# mass_slit.net
KiCad netlist of a schematic drawn in EAGLE
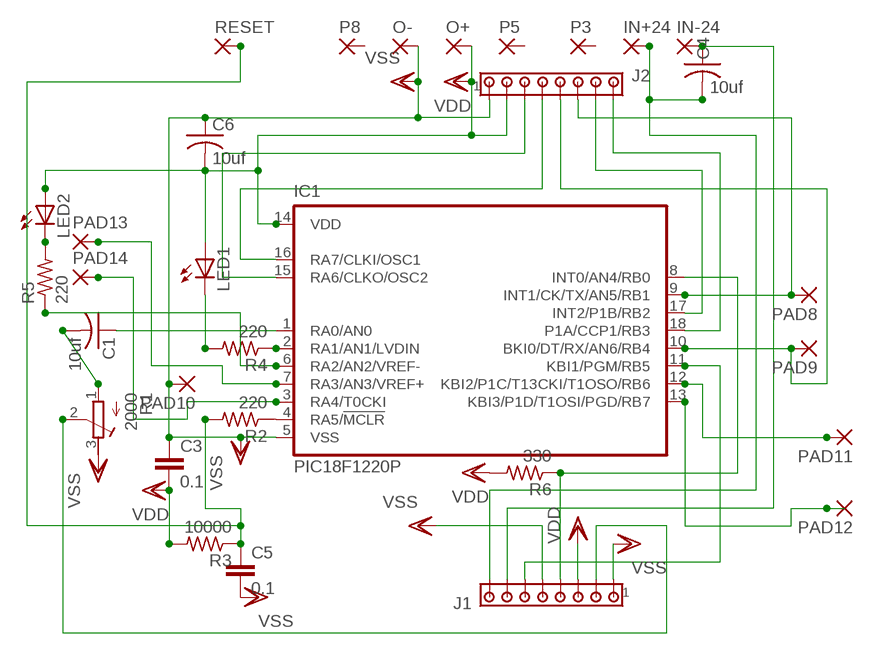
[diagram p0: schematic, sheet 1]

(export (version "E")
  (design (tool "Eeschema 10.0.6"))
  (components
    (comp (ref "C1")
      (value "10uf")
      (footprint "eagle-import:C025-040X050")
      (libsource (lib "eagle-import") (part "C-US025-040X050"))
    )
    (comp (ref "C3")
      (value "0.1")
      (footprint "eagle-import:C5B2.5")
      (libsource (lib "eagle-import") (part "C5/2.5"))
    )
    (comp (ref "C4")
      (value "10uf")
      (footprint "eagle-import:C025-040X050")
      (libsource (lib "eagle-import") (part "C-US025-040X050"))
    )
    (comp (ref "C5")
      (value "0.1")
      (footprint "eagle-import:C5B2.5")
      (libsource (lib "eagle-import") (part "C5/2.5"))
    )
    (comp (ref "C6")
      (value "10uf")
      (footprint "eagle-import:C025-040X050")
      (libsource (lib "eagle-import") (part "C-US025-040X050"))
    )
    (comp (ref "IC1")
      (value "PIC18F1220P")
      (footprint "eagle-import:DIL18")
      (fields (field (name "MF") "MICROCHIP") (field (name "MPN") "PIC18F1220-I/P"))
      (libsource (lib "eagle-import") (part "PIC18F120P2"))
    )
    (comp (ref "IN+24")
      (value "1,6/0,9")
      (footprint "eagle-import:1,6_0,9")
      (libsource (lib "eagle-import") (part "1,6/0,9"))
    )
    (comp (ref "IN-24")
      (value "1,6/0,9")
      (footprint "eagle-import:1,6_0,9")
      (libsource (lib "eagle-import") (part "1,6/0,9"))
    )
    (comp (ref "J1")
      (value "MTA08-100")
      (footprint "eagle-import:10X08MTA")
      (libsource (lib "eagle-import") (part "MTA08-100"))
    )
    (comp (ref "J2")
      (value "MTA08-100")
      (footprint "eagle-import:10X08MTA")
      (libsource (lib "eagle-import") (part "MTA08-100"))
    )
    (comp (ref "LED1")
      (value "LED3MM")
      (footprint "eagle-import:LED3MM")
      (libsource (lib "eagle-import") (part "LED3MM"))
    )
    (comp (ref "LED2")
      (value "LED3MM")
      (footprint "eagle-import:LED3MM")
      (libsource (lib "eagle-import") (part "LED3MM"))
    )
    (comp (ref "O+")
      (value "1,6/0,9")
      (footprint "eagle-import:1,6_0,9")
      (libsource (lib "eagle-import") (part "1,6/0,9"))
    )
    (comp (ref "O-")
      (value "1,6/0,9")
      (footprint "eagle-import:1,6_0,9")
      (libsource (lib "eagle-import") (part "1,6/0,9"))
    )
    (comp (ref "P3")
      (value "1,6/0,9")
      (footprint "eagle-import:1,6_0,9")
      (libsource (lib "eagle-import") (part "1,6/0,9"))
    )
    (comp (ref "P5")
      (value "1,6/0,9")
      (footprint "eagle-import:1,6_0,9")
      (libsource (lib "eagle-import") (part "1,6/0,9"))
    )
    (comp (ref "P8")
      (value "1,6/0,9")
      (footprint "eagle-import:1,6_0,9")
      (libsource (lib "eagle-import") (part "1,6/0,9"))
    )
    (comp (ref "PAD8")
      (value "1,6/0,9")
      (footprint "eagle-import:1,6_0,9")
      (libsource (lib "eagle-import") (part "1,6/0,9"))
    )
    (comp (ref "PAD9")
      (value "1,6/0,9")
      (footprint "eagle-import:1,6_0,9")
      (libsource (lib "eagle-import") (part "1,6/0,9"))
    )
    (comp (ref "PAD10")
      (value "1,6/0,9")
      (footprint "eagle-import:1,6_0,9")
      (libsource (lib "eagle-import") (part "1,6/0,9"))
    )
    (comp (ref "PAD11")
      (value "1,6/0,9")
      (footprint "eagle-import:1,6_0,9")
      (libsource (lib "eagle-import") (part "1,6/0,9"))
    )
    (comp (ref "PAD12")
      (value "1,6/0,9")
      (footprint "eagle-import:1,6_0,9")
      (libsource (lib "eagle-import") (part "1,6/0,9"))
    )
    (comp (ref "PAD13")
      (value "1,6/0,9")
      (footprint "eagle-import:1,6_0,9")
      (libsource (lib "eagle-import") (part "1,6/0,9"))
    )
    (comp (ref "PAD14")
      (value "1,6/0,9")
      (footprint "eagle-import:1,6_0,9")
      (libsource (lib "eagle-import") (part "1,6/0,9"))
    )
    (comp (ref "R1")
      (value "2000")
      (footprint "eagle-import:RTRIM3339P")
      (libsource (lib "eagle-import") (part "R-TRIMM3339P"))
    )
    (comp (ref "R2")
      (value "220")
      (footprint "eagle-import:0204V")
      (libsource (lib "eagle-import") (part "R-US_0204/2V"))
    )
    (comp (ref "R3")
      (value "10000")
      (footprint "eagle-import:0204V")
      (libsource (lib "eagle-import") (part "R-US_0204/2V"))
    )
    (comp (ref "R4")
      (value "220")
      (footprint "eagle-import:0204V")
      (libsource (lib "eagle-import") (part "R-US_0204/2V"))
    )
    (comp (ref "R5")
      (value "220")
      (footprint "eagle-import:0204V")
      (libsource (lib "eagle-import") (part "R-US_0204/2V"))
    )
    (comp (ref "R6")
      (value "330")
      (footprint "eagle-import:0204V")
      (libsource (lib "eagle-import") (part "R-US_0204/2V"))
    )
    (comp (ref "RESET")
      (value "1,6/0,9")
      (footprint "eagle-import:1,6_0,9")
      (libsource (lib "eagle-import") (part "1,6/0,9"))
    )
  )
  (nets
    (net (code "1") (name "Net-(IC1-BKI0{slash}DT{slash}RX{slash}AN6{slash}RB4)") (class "Default")
      (node (ref "IC1") (pin "10") (pinfunction "BKI0/DT/RX/AN6/RB4_10") (pintype "bidirectional"))
      (node (ref "J2") (pin "5") (pinfunction "5_5") (pintype "passive"))
      (node (ref "PAD9") (pin "1") (pinfunction "P_1") (pintype "passive"))
    )
    (net (code "2") (name "Net-(IC1-INT0{slash}AN4{slash}RB0)") (class "Default")
      (node (ref "IC1") (pin "8") (pinfunction "INT0/AN4/RB0_8") (pintype "bidirectional"))
      (node (ref "J1") (pin "4") (pinfunction "4_4") (pintype "passive"))
      (node (ref "R6") (pin "1") (pinfunction "1_1") (pintype "passive"))
    )
    (net (code "3") (name "Net-(IC1-INT1{slash}CK{slash}TX{slash}AN5{slash}RB1)") (class "Default")
      (node (ref "IC1") (pin "9") (pinfunction "INT1/CK/TX/AN5/RB1_9") (pintype "bidirectional"))
      (node (ref "J2") (pin "6") (pinfunction "6_6") (pintype "passive"))
      (node (ref "PAD8") (pin "1") (pinfunction "P_1") (pintype "passive"))
    )
    (net (code "4") (name "Net-(IC1-INT2{slash}P1B{slash}RB2)") (class "Default")
      (node (ref "IC1") (pin "17") (pinfunction "INT2/P1B/RB2_17") (pintype "bidirectional"))
      (node (ref "J2") (pin "7") (pinfunction "7_7") (pintype "passive"))
    )
    (net (code "5") (name "Net-(IC1-KBI1{slash}PGM{slash}RB5)") (class "Default")
      (node (ref "IC1") (pin "11") (pinfunction "KBI1/PGM/RB5_11") (pintype "bidirectional"))
      (node (ref "J1") (pin "6") (pinfunction "6_6") (pintype "passive"))
    )
    (net (code "6") (name "Net-(IC1-KBI2{slash}P1C{slash}T13CKI{slash}T1OSO{slash}RB6)") (class "Default")
      (node (ref "IC1") (pin "12") (pinfunction "KBI2/P1C/T13CKI/T1OSO/RB6_12") (pintype "bidirectional"))
      (node (ref "PAD11") (pin "1") (pinfunction "P_1") (pintype "passive"))
    )
    (net (code "7") (name "Net-(IC1-KBI3{slash}P1D{slash}T1OSI{slash}PGD{slash}RB7)") (class "Default")
      (node (ref "IC1") (pin "13") (pinfunction "KBI3/P1D/T1OSI/PGD/RB7_13") (pintype "bidirectional"))
      (node (ref "PAD12") (pin "1") (pinfunction "P_1") (pintype "passive"))
    )
    (net (code "8") (name "Net-(IC1-P1A{slash}CCP1{slash}RB3)") (class "Default")
      (node (ref "IC1") (pin "18") (pinfunction "P1A/CCP1/RB3_18") (pintype "bidirectional"))
      (node (ref "J2") (pin "8") (pinfunction "8_8") (pintype "passive"))
    )
    (net (code "9") (name "Net-(IC1-RA0{slash}AN0)") (class "Default")
      (node (ref "C1") (pin "1") (pinfunction "1_1") (pintype "passive"))
      (node (ref "IC1") (pin "1") (pinfunction "RA0/AN0_1") (pintype "bidirectional"))
    )
    (net (code "10") (name "Net-(IC1-RA1{slash}AN1{slash}LVDIN)") (class "Default")
      (node (ref "IC1") (pin "2") (pinfunction "RA1/AN1/LVDIN_2") (pintype "bidirectional"))
      (node (ref "R4") (pin "1") (pinfunction "1_1") (pintype "passive"))
    )
    (net (code "11") (name "Net-(IC1-RA2{slash}AN2{slash}VREF-)") (class "Default")
      (node (ref "IC1") (pin "6") (pinfunction "RA2/AN2/VREF-_6") (pintype "bidirectional"))
      (node (ref "R5") (pin "1") (pinfunction "1_1") (pintype "passive"))
    )
    (net (code "12") (name "Net-(IC1-RA3{slash}AN3{slash}VREF+)") (class "Default")
      (node (ref "IC1") (pin "7") (pinfunction "RA3/AN3/VREF+_7") (pintype "bidirectional"))
      (node (ref "PAD13") (pin "1") (pinfunction "P_1") (pintype "passive"))
    )
    (net (code "13") (name "Net-(IC1-RA4{slash}T0CKI)") (class "Default")
      (node (ref "IC1") (pin "3") (pinfunction "RA4/T0CKI_3") (pintype "bidirectional"))
      (node (ref "PAD14") (pin "1") (pinfunction "P_1") (pintype "passive"))
    )
    (net (code "14") (name "Net-(IC1-RA5{slash}~{MCLR})") (class "Default")
      (node (ref "IC1") (pin "4") (pinfunction "RA5/~{MCLR}_4") (pintype "input"))
      (node (ref "R2") (pin "1") (pinfunction "1_1") (pintype "passive"))
    )
    (net (code "15") (name "Net-(IC1-RA6{slash}CLKO{slash}OSC2)") (class "Default")
      (node (ref "IC1") (pin "15") (pinfunction "RA6/CLKO/OSC2_15") (pintype "bidirectional"))
      (node (ref "J2") (pin "3") (pinfunction "3_3") (pintype "passive"))
    )
    (net (code "16") (name "Net-(IC1-RA7{slash}CLKI{slash}OSC1)") (class "Default")
      (node (ref "IC1") (pin "16") (pinfunction "RA7/CLKI/OSC1_16") (pintype "bidirectional"))
      (node (ref "J2") (pin "4") (pinfunction "4_4") (pintype "passive"))
    )
    (net (code "17") (name "Net-(IN+24-P)") (class "Default")
      (node (ref "C4") (pin "2") (pinfunction "2_2") (pintype "passive"))
      (node (ref "IN+24") (pin "1") (pinfunction "P_1") (pintype "passive"))
      (node (ref "J1") (pin "8") (pinfunction "8_8") (pintype "passive"))
    )
    (net (code "18") (name "Net-(IN-24-P)") (class "Default")
      (node (ref "C4") (pin "1") (pinfunction "1_1") (pintype "passive"))
      (node (ref "IN-24") (pin "1") (pinfunction "P_1") (pintype "passive"))
      (node (ref "J1") (pin "7") (pinfunction "7_7") (pintype "passive"))
    )
    (net (code "19") (name "Net-(LED1-C)") (class "Default")
      (node (ref "LED1") (pin "K") (pinfunction "C_K") (pintype "passive"))
      (node (ref "R4") (pin "2") (pinfunction "2_2") (pintype "passive"))
    )
    (net (code "20") (name "Net-(LED2-C)") (class "Default")
      (node (ref "LED2") (pin "K") (pinfunction "C_K") (pintype "passive"))
      (node (ref "R5") (pin "2") (pinfunction "2_2") (pintype "passive"))
    )
    (net (code "21") (name "Net-(R1-A)") (class "Default")
      (node (ref "C1") (pin "2") (pinfunction "2_2") (pintype "passive"))
      (node (ref "R1") (pin "1") (pinfunction "A_1") (pintype "passive"))
    )
    (net (code "22") (name "Net-(R1-S)") (class "Default")
      (node (ref "J1") (pin "2") (pinfunction "2_2") (pintype "passive"))
      (node (ref "R1") (pin "2") (pinfunction "S_2") (pintype "passive"))
    )
    (net (code "23") (name "Net-(RESET-P)") (class "Default")
      (node (ref "C5") (pin "1") (pinfunction "1_1") (pintype "passive"))
      (node (ref "R2") (pin "2") (pinfunction "2_2") (pintype "passive"))
      (node (ref "R3") (pin "1") (pinfunction "1_1") (pintype "passive"))
      (node (ref "RESET") (pin "1") (pinfunction "P_1") (pintype "passive"))
    )
    (net (code "24") (name "VDD") (class "Default")
      (node (ref "C3") (pin "2") (pinfunction "2_2") (pintype "passive"))
      (node (ref "C6") (pin "2") (pinfunction "2_2") (pintype "passive"))
      (node (ref "IC1") (pin "14") (pinfunction "VDD_14") (pintype "power_in"))
      (node (ref "J1") (pin "3") (pinfunction "3_3") (pintype "passive"))
      (node (ref "J2") (pin "2") (pinfunction "2_2") (pintype "passive"))
      (node (ref "LED1") (pin "A") (pinfunction "A_A") (pintype "passive"))
      (node (ref "LED2") (pin "A") (pinfunction "A_A") (pintype "passive"))
      (node (ref "O+") (pin "1") (pinfunction "P_1") (pintype "passive"))
      (node (ref "R3") (pin "2") (pinfunction "2_2") (pintype "passive"))
      (node (ref "R6") (pin "2") (pinfunction "2_2") (pintype "passive"))
    )
    (net (code "25") (name "VSS") (class "Default")
      (node (ref "C3") (pin "1") (pinfunction "1_1") (pintype "passive"))
      (node (ref "C5") (pin "2") (pinfunction "2_2") (pintype "passive"))
      (node (ref "C6") (pin "1") (pinfunction "1_1") (pintype "passive"))
      (node (ref "IC1") (pin "5") (pinfunction "VSS_5") (pintype "power_in"))
      (node (ref "J1") (pin "1") (pinfunction "1_1") (pintype "passive"))
      (node (ref "J1") (pin "5") (pinfunction "5_5") (pintype "passive"))
      (node (ref "J2") (pin "1") (pinfunction "1_1") (pintype "passive"))
      (node (ref "O-") (pin "1") (pinfunction "P_1") (pintype "passive"))
      (node (ref "PAD10") (pin "1") (pinfunction "P_1") (pintype "passive"))
      (node (ref "R1") (pin "3") (pinfunction "E_3") (pintype "passive"))
    )
    (net (code "26") (name "unconnected-(P3-P-Pad1)") (class "Default")
      (node (ref "P3") (pin "1") (pinfunction "P_1") (pintype "passive"))
    )
    (net (code "27") (name "unconnected-(P5-P-Pad1)") (class "Default")
      (node (ref "P5") (pin "1") (pinfunction "P_1") (pintype "passive"))
    )
    (net (code "28") (name "unconnected-(P8-P-Pad1)") (class "Default")
      (node (ref "P8") (pin "1") (pinfunction "P_1") (pintype "passive"))
    )
  )
)
